# DB4100_MCU_v0_3.net
KiCad netlist of a schematic drawn in Altium Designer
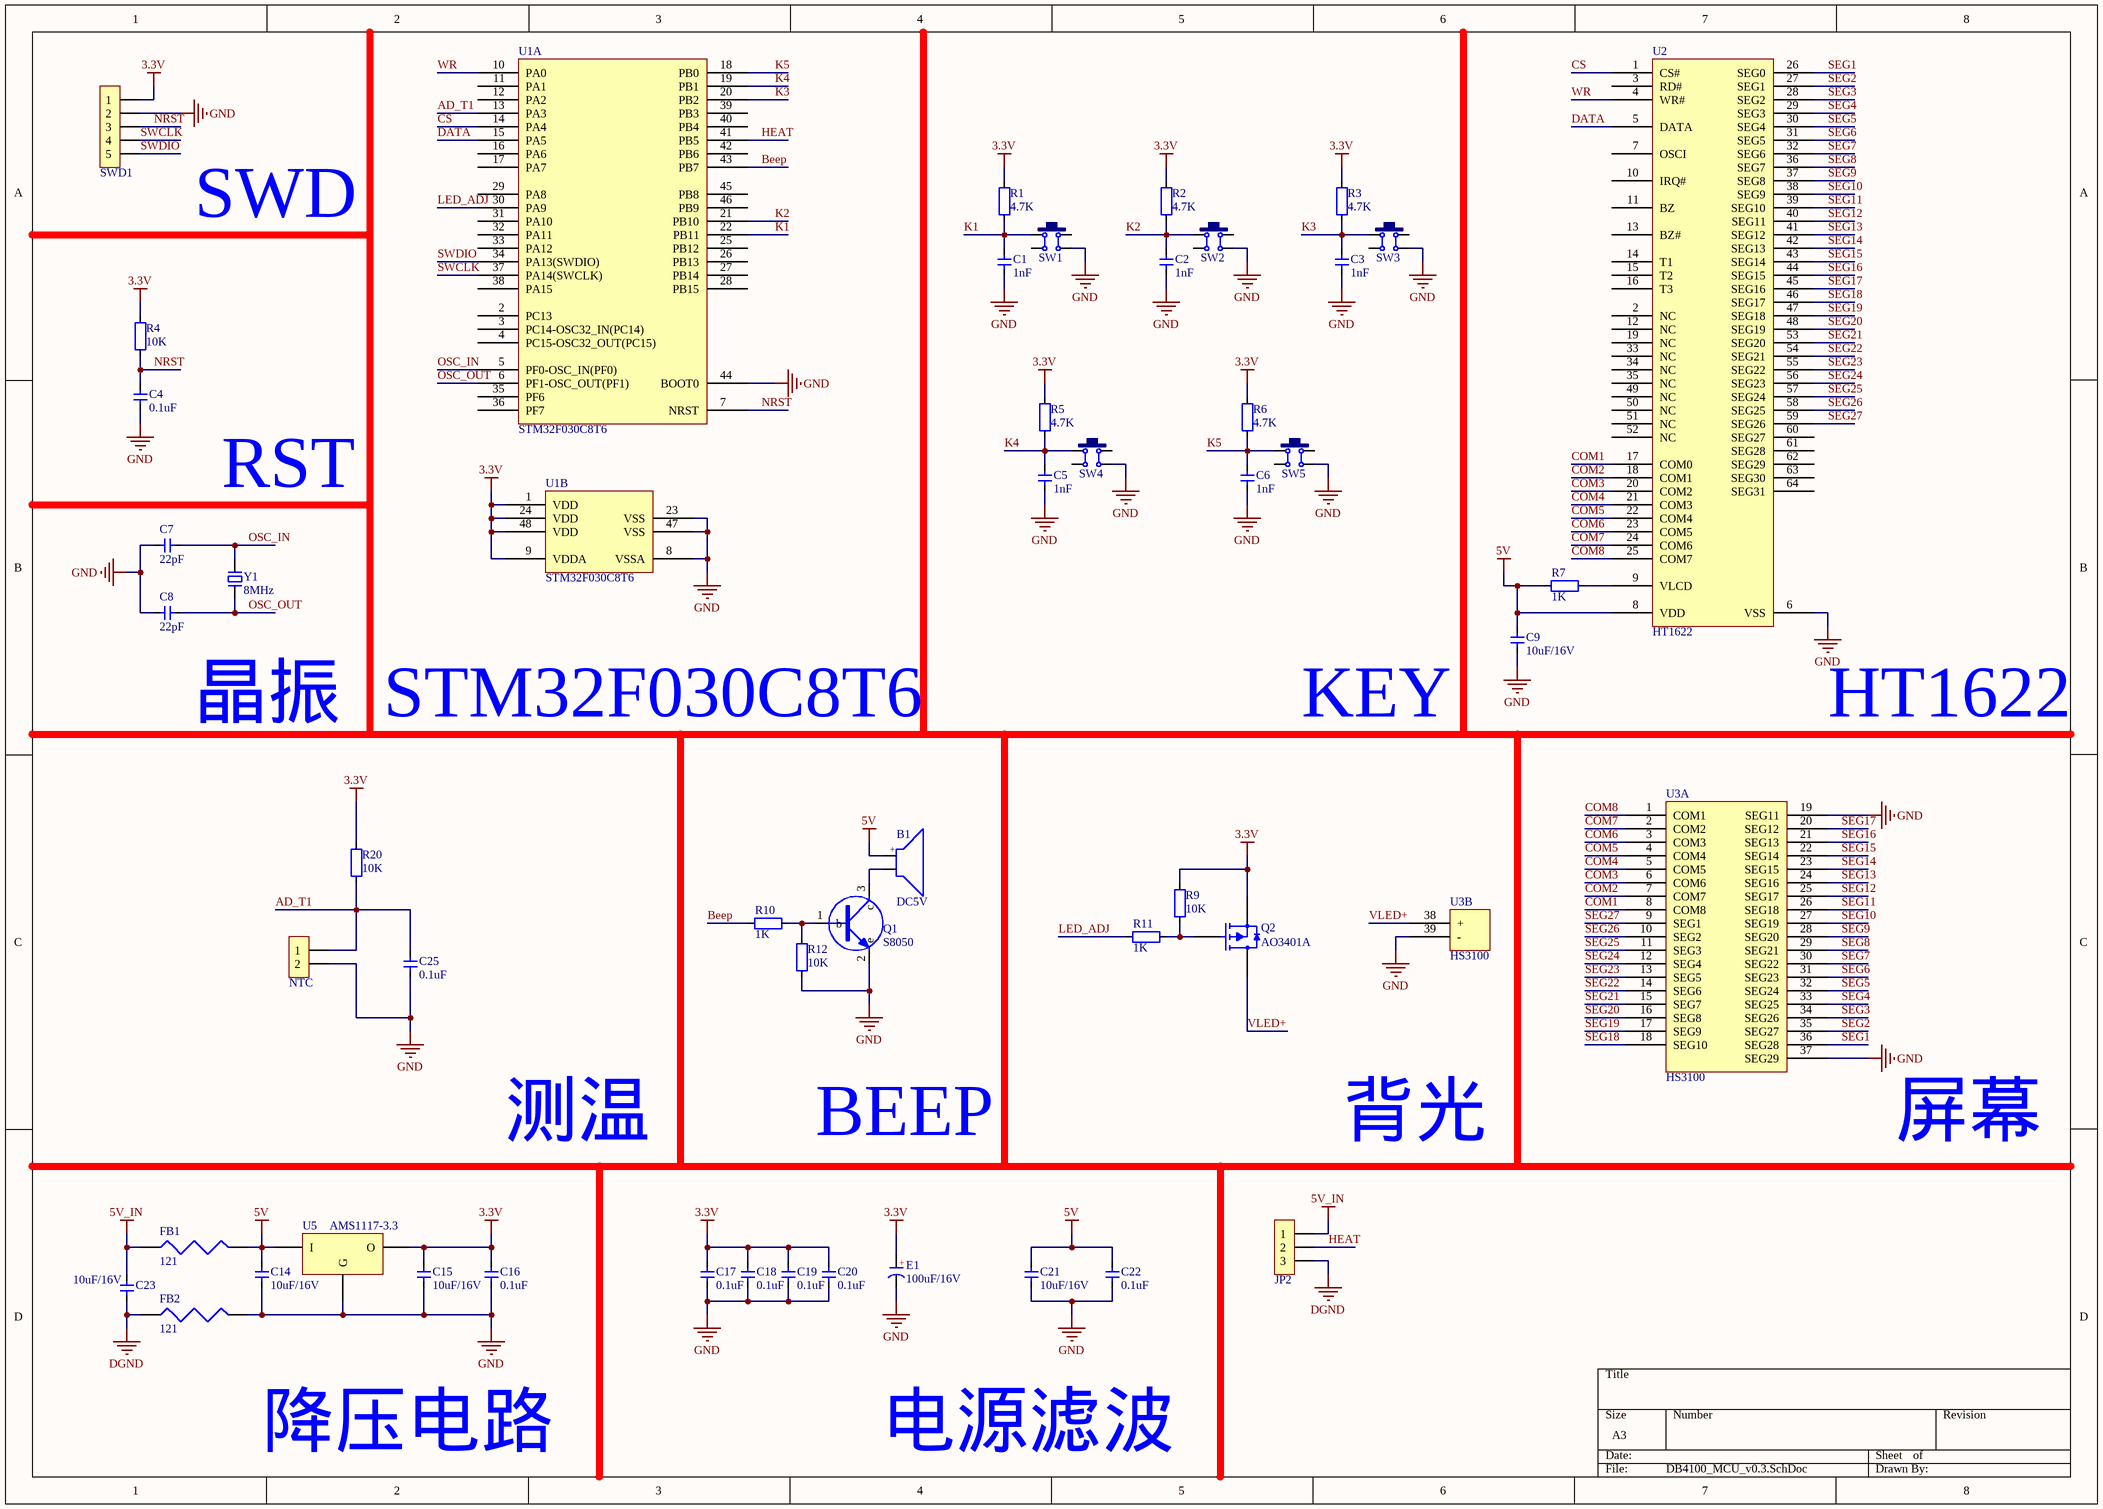
[diagram p0: DB4100_MCU_v0.3.SchDoc]

(export (version "E")
  (design (tool "Eeschema 10.0.6"))
  (components
    (comp (ref "B1")
      (value "DC5V")
      (footprint "BEEP 7.6X12X7.5")
      (description "蜂鸣器")
      (fields (field (name "版权归属") "源创客"))
      (libsource (lib "模块器件") (part "BEEP"))
    )
    (comp (ref "C1")
      (value "1nF")
      (footprint "C 0603")
      (description "无极性贴片电容")
      (fields (field (name "版权归属") "源创客"))
      (libsource (lib "电容") (part "C"))
    )
    (comp (ref "C2")
      (value "1nF")
      (footprint "C 0603")
      (description "无极性贴片电容")
      (fields (field (name "版权归属") "源创客"))
      (libsource (lib "电容") (part "C"))
    )
    (comp (ref "C3")
      (value "1nF")
      (footprint "C 0603")
      (description "无极性贴片电容")
      (fields (field (name "版权归属") "源创客"))
      (libsource (lib "电容") (part "C"))
    )
    (comp (ref "C4")
      (value "0.1uF")
      (footprint "C 0603")
      (description "无极性贴片电容")
      (fields (field (name "版权归属") "源创客"))
      (libsource (lib "电容") (part "C"))
    )
    (comp (ref "C5")
      (value "1nF")
      (footprint "C 0603")
      (description "无极性贴片电容")
      (fields (field (name "版权归属") "源创客"))
      (libsource (lib "电容") (part "C"))
    )
    (comp (ref "C6")
      (value "1nF")
      (footprint "C 0603")
      (description "无极性贴片电容")
      (fields (field (name "版权归属") "源创客"))
      (libsource (lib "电容") (part "C"))
    )
    (comp (ref "C7")
      (value "22pF")
      (footprint "C 0603")
      (description "无极性贴片电容")
      (fields (field (name "版权归属") "源创客"))
      (libsource (lib "电容") (part "C"))
    )
    (comp (ref "C8")
      (value "22pF")
      (footprint "C 0603")
      (description "无极性贴片电容")
      (fields (field (name "版权归属") "源创客"))
      (libsource (lib "电容") (part "C"))
    )
    (comp (ref "C9")
      (value "10uF/16V")
      (footprint "C 0805")
      (description "无极性贴片电容")
      (fields (field (name "版权归属") "源创客"))
      (libsource (lib "电容") (part "C"))
    )
    (comp (ref "C14")
      (value "10uF/16V")
      (footprint "C 0805")
      (description "无极性贴片电容")
      (fields (field (name "版权归属") "源创客"))
      (libsource (lib "电容") (part "C"))
    )
    (comp (ref "C15")
      (value "10uF/16V")
      (footprint "C 0805")
      (description "无极性贴片电容")
      (fields (field (name "版权归属") "源创客"))
      (libsource (lib "电容") (part "C"))
    )
    (comp (ref "C16")
      (value "0.1uF")
      (footprint "C 0603")
      (description "无极性贴片电容")
      (fields (field (name "版权归属") "源创客"))
      (libsource (lib "电容") (part "C"))
    )
    (comp (ref "C17")
      (value "0.1uF")
      (footprint "C 0603")
      (description "无极性贴片电容")
      (fields (field (name "版权归属") "源创客"))
      (libsource (lib "电容") (part "C"))
    )
    (comp (ref "C18")
      (value "0.1uF")
      (footprint "C 0603")
      (description "无极性贴片电容")
      (fields (field (name "版权归属") "源创客"))
      (libsource (lib "电容") (part "C"))
    )
    (comp (ref "C19")
      (value "0.1uF")
      (footprint "C 0603")
      (description "无极性贴片电容")
      (fields (field (name "版权归属") "源创客"))
      (libsource (lib "电容") (part "C"))
    )
    (comp (ref "C20")
      (value "0.1uF")
      (footprint "C 0603")
      (description "无极性贴片电容")
      (fields (field (name "版权归属") "源创客"))
      (libsource (lib "电容") (part "C"))
    )
    (comp (ref "C21")
      (value "10uF/16V")
      (footprint "C 0805")
      (description "无极性贴片电容")
      (fields (field (name "版权归属") "源创客"))
      (libsource (lib "电容") (part "C"))
    )
    (comp (ref "C22")
      (value "0.1uF")
      (footprint "C 0603")
      (description "无极性贴片电容")
      (fields (field (name "版权归属") "源创客"))
      (libsource (lib "电容") (part "C"))
    )
    (comp (ref "C23")
      (value "10uF/16V")
      (footprint "C 0805")
      (description "无极性贴片电容")
      (fields (field (name "版权归属") "源创客"))
      (libsource (lib "电容") (part "C"))
    )
    (comp (ref "C25")
      (value "0.1uF")
      (footprint "C 0603")
      (description "无极性贴片电容")
      (fields (field (name "版权归属") "源创客"))
      (libsource (lib "电容") (part "C"))
    )
    (comp (ref "E1")
      (value "100uF/16V")
      (footprint "CAP 2.0*5*11 - BK")
      (description "直插电解电容")
      (fields (field (name "版权归属") "源创客"))
      (libsource (lib "电容") (part "C-CAP"))
    )
    (comp (ref "FB1")
      (value "121")
      (footprint "L 0805")
      (description "磁珠")
      (libsource (lib "电感") (part "FB"))
    )
    (comp (ref "FB2")
      (value "121")
      (footprint "L 0805")
      (description "磁珠")
      (libsource (lib "电感") (part "FB"))
    )
    (comp (ref "JP2")
      (value "HDR-1X3")
      (footprint "XH2.54-3P")
      (description "3P接插件")
      (fields (field (name "版权归属") "源创客"))
      (libsource (lib "排针-排母") (part "Header 3"))
    )
    (comp (ref "NTC")
      (value "HDR-1X2")
      (footprint "XH2.54-2P")
      (description "2P接插件")
      (fields (field (name "版权归属") "源创客"))
      (libsource (lib "排针-排母") (part "Header 2"))
    )
    (comp (ref "Q1") (value "S8050") (footprint "SOT23-3L") (libsource (lib "三极管") (part "NPN")))
    (comp (ref "Q2")
      (value "AO3401A")
      (footprint "SOT23-3")
      (description "P-MOS")
      (libsource (lib "三极管") (part "AO3401A"))
    )
    (comp (ref "R1")
      (value "4.7K")
      (footprint "R 0603")
      (description "贴片电阻")
      (fields (field (name "版权归属") "源创客"))
      (libsource (lib "电阻") (part "R"))
    )
    (comp (ref "R2")
      (value "4.7K")
      (footprint "R 0603")
      (description "贴片电阻")
      (fields (field (name "版权归属") "源创客"))
      (libsource (lib "电阻") (part "R"))
    )
    (comp (ref "R3")
      (value "4.7K")
      (footprint "R 0603")
      (description "贴片电阻")
      (fields (field (name "版权归属") "源创客"))
      (libsource (lib "电阻") (part "R"))
    )
    (comp (ref "R4")
      (value "10K")
      (footprint "R 0603")
      (description "贴片电阻")
      (fields (field (name "版权归属") "源创客"))
      (libsource (lib "电阻") (part "R"))
    )
    (comp (ref "R5")
      (value "4.7K")
      (footprint "R 0603")
      (description "贴片电阻")
      (fields (field (name "版权归属") "源创客"))
      (libsource (lib "电阻") (part "R"))
    )
    (comp (ref "R6")
      (value "4.7K")
      (footprint "R 0603")
      (description "贴片电阻")
      (fields (field (name "版权归属") "源创客"))
      (libsource (lib "电阻") (part "R"))
    )
    (comp (ref "R7")
      (value "1K")
      (footprint "R 0603")
      (description "贴片电阻")
      (fields (field (name "版权归属") "源创客"))
      (libsource (lib "") (part "R_1"))
    )
    (comp (ref "R9")
      (value "10K")
      (footprint "R 0603")
      (description "贴片电阻")
      (fields (field (name "版权归属") "源创客"))
      (libsource (lib "电阻") (part "R"))
    )
    (comp (ref "R10")
      (value "1K")
      (footprint "R 0603")
      (description "贴片电阻")
      (fields (field (name "版权归属") "源创客"))
      (libsource (lib "") (part "R_1"))
    )
    (comp (ref "R11")
      (value "1K")
      (footprint "R 0603")
      (description "贴片电阻")
      (fields (field (name "版权归属") "源创客"))
      (libsource (lib "") (part "R_1"))
    )
    (comp (ref "R12")
      (value "10K")
      (footprint "R 0603")
      (description "贴片电阻")
      (fields (field (name "版权归属") "源创客"))
      (libsource (lib "电阻") (part "R"))
    )
    (comp (ref "R20")
      (value "10K")
      (footprint "R 0603")
      (description "贴片电阻")
      (fields (field (name "版权归属") "源创客"))
      (libsource (lib "电阻") (part "R"))
    )
    (comp (ref "SW1")
      (value "6x6x5")
      (footprint "TSW SMD-6*6*7")
      (description "贴片6x6轻触开关")
      (fields (field (name "版权归属") "源创客"))
      (libsource (lib "按键") (part "TSW SMD-6x6"))
    )
    (comp (ref "SW2")
      (value "6x6x5")
      (footprint "TSW SMD-6*6*7")
      (description "贴片6x6轻触开关")
      (fields (field (name "版权归属") "源创客"))
      (libsource (lib "按键") (part "TSW SMD-6x6"))
    )
    (comp (ref "SW3")
      (value "6x6x5")
      (footprint "TSW SMD-6*6*7")
      (description "贴片6x6轻触开关")
      (fields (field (name "版权归属") "源创客"))
      (libsource (lib "按键") (part "TSW SMD-6x6"))
    )
    (comp (ref "SW4")
      (value "6x6x5")
      (footprint "TSW SMD-6*6*7")
      (description "贴片6x6轻触开关")
      (fields (field (name "版权归属") "源创客"))
      (libsource (lib "按键") (part "TSW SMD-6x6"))
    )
    (comp (ref "SW5")
      (value "6x6x5")
      (footprint "TSW SMD-6*6*7")
      (description "贴片6x6轻触开关")
      (fields (field (name "版权归属") "源创客"))
      (libsource (lib "按键") (part "TSW SMD-6x6"))
    )
    (comp (ref "SWD1")
      (value "HDR-1X5")
      (footprint "XH2.54-5P")
      (description "5P接插件")
      (fields (field (name "版权归属") "源创客"))
      (libsource (lib "排针-排母") (part "Header 5"))
    )
    (comp (ref "U1")
      (value "STM32F030C8T6")
      (footprint "STM32F030C8T6")
      (libsource (lib "STM32系列单片机") (part "STM32F030C8T6"))
    )
    (comp (ref "U2")
      (value "HT1622")
      (footprint "HT1622")
      (description "LCD驱动，64引脚")
      (libsource (lib "显示芯片") (part "HT1622"))
    )
    (comp (ref "U3")
      (value "HS3100")
      (footprint "HS3100")
      (description "HS3100的屏幕")
      (libsource (lib "显示屏幕") (part "HS3100"))
    )
    (comp (ref "U5")
      (value "AMS1117-3.3")
      (footprint "AMS1117-3.3")
      (description "转3.3V电压")
      (libsource (lib "变压器") (part "AMS1117-3.3"))
    )
    (comp (ref "Y1")
      (value "8MHz")
      (footprint "XTAL-49S SMD")
      (description "2脚晶振")
      (fields (field (name "版权归属") "源创客"))
      (libsource (lib "晶振") (part "XTAL-2"))
    )
  )
  (nets
    (net (code "1") (name "/AD_T1") (class "Default")
      (node (ref "C25") (pin "1") (pinfunction "1_1") (pintype "passive"))
      (node (ref "NTC") (pin "1") (pinfunction "1_1") (pintype "passive"))
      (node (ref "R20") (pin "1") (pinfunction "1_1") (pintype "passive"))
      (node (ref "U1") (pin "13") (pinfunction "PA3_13") (pintype "passive"))
    )
    (net (code "2") (name "/Beep") (class "Default")
      (node (ref "R10") (pin "1") (pinfunction "1_1") (pintype "passive"))
      (node (ref "U1") (pin "43") (pinfunction "PB7_43") (pintype "passive"))
    )
    (net (code "3") (name "/COM1") (class "Default")
      (node (ref "U2") (pin "17") (pinfunction "COM0_17") (pintype "passive"))
      (node (ref "U3") (pin "8") (pinfunction "COM8_8") (pintype "passive"))
    )
    (net (code "4") (name "/COM2") (class "Default")
      (node (ref "U2") (pin "18") (pinfunction "COM1_18") (pintype "passive"))
      (node (ref "U3") (pin "7") (pinfunction "COM7_7") (pintype "passive"))
    )
    (net (code "5") (name "/COM3") (class "Default")
      (node (ref "U2") (pin "20") (pinfunction "COM2_20") (pintype "passive"))
      (node (ref "U3") (pin "6") (pinfunction "COM6_6") (pintype "passive"))
    )
    (net (code "6") (name "/COM4") (class "Default")
      (node (ref "U2") (pin "21") (pinfunction "COM3_21") (pintype "passive"))
      (node (ref "U3") (pin "5") (pinfunction "COM5_5") (pintype "passive"))
    )
    (net (code "7") (name "/COM5") (class "Default")
      (node (ref "U2") (pin "22") (pinfunction "COM4_22") (pintype "passive"))
      (node (ref "U3") (pin "4") (pinfunction "COM4_4") (pintype "passive"))
    )
    (net (code "8") (name "/COM6") (class "Default")
      (node (ref "U2") (pin "23") (pinfunction "COM5_23") (pintype "passive"))
      (node (ref "U3") (pin "3") (pinfunction "COM3_3") (pintype "passive"))
    )
    (net (code "9") (name "/COM7") (class "Default")
      (node (ref "U2") (pin "24") (pinfunction "COM6_24") (pintype "passive"))
      (node (ref "U3") (pin "2") (pinfunction "COM2_2") (pintype "passive"))
    )
    (net (code "10") (name "/COM8") (class "Default")
      (node (ref "U2") (pin "25") (pinfunction "COM7_25") (pintype "passive"))
      (node (ref "U3") (pin "1") (pinfunction "COM1_1") (pintype "passive"))
    )
    (net (code "11") (name "/CS") (class "Default")
      (node (ref "U1") (pin "14") (pinfunction "PA4_14") (pintype "passive"))
      (node (ref "U2") (pin "1") (pinfunction "CS#_1") (pintype "passive"))
    )
    (net (code "12") (name "/DATA") (class "Default")
      (node (ref "U1") (pin "15") (pinfunction "PA5_15") (pintype "passive"))
      (node (ref "U2") (pin "5") (pinfunction "DATA_5") (pintype "passive"))
    )
    (net (code "13") (name "/HEAT") (class "Default")
      (node (ref "JP2") (pin "2") (pinfunction "2_2") (pintype "passive"))
      (node (ref "U1") (pin "41") (pinfunction "PB5_41") (pintype "passive"))
    )
    (net (code "14") (name "/K1") (class "Default")
      (node (ref "C1") (pin "2") (pinfunction "2_2") (pintype "passive"))
      (node (ref "R1") (pin "1") (pinfunction "1_1") (pintype "passive"))
      (node (ref "SW1") (pin "1") (pinfunction "1_1") (pintype "passive"))
      (node (ref "U1") (pin "22") (pinfunction "PB11_22") (pintype "passive"))
    )
    (net (code "15") (name "/K2") (class "Default")
      (node (ref "C2") (pin "2") (pinfunction "2_2") (pintype "passive"))
      (node (ref "R2") (pin "1") (pinfunction "1_1") (pintype "passive"))
      (node (ref "SW2") (pin "1") (pinfunction "1_1") (pintype "passive"))
      (node (ref "U1") (pin "21") (pinfunction "PB10_21") (pintype "passive"))
    )
    (net (code "16") (name "/K3") (class "Default")
      (node (ref "C3") (pin "2") (pinfunction "2_2") (pintype "passive"))
      (node (ref "R3") (pin "1") (pinfunction "1_1") (pintype "passive"))
      (node (ref "SW3") (pin "1") (pinfunction "1_1") (pintype "passive"))
      (node (ref "U1") (pin "20") (pinfunction "PB2_20") (pintype "passive"))
    )
    (net (code "17") (name "/K4") (class "Default")
      (node (ref "C5") (pin "2") (pinfunction "2_2") (pintype "passive"))
      (node (ref "R5") (pin "1") (pinfunction "1_1") (pintype "passive"))
      (node (ref "SW4") (pin "1") (pinfunction "1_1") (pintype "passive"))
      (node (ref "U1") (pin "19") (pinfunction "PB1_19") (pintype "passive"))
    )
    (net (code "18") (name "/K5") (class "Default")
      (node (ref "C6") (pin "2") (pinfunction "2_2") (pintype "passive"))
      (node (ref "R6") (pin "1") (pinfunction "1_1") (pintype "passive"))
      (node (ref "SW5") (pin "1") (pinfunction "1_1") (pintype "passive"))
      (node (ref "U1") (pin "18") (pinfunction "PB0_18") (pintype "passive"))
    )
    (net (code "19") (name "/LED_ADJ") (class "Default")
      (node (ref "R11") (pin "1") (pinfunction "1_1") (pintype "passive"))
      (node (ref "U1") (pin "30") (pinfunction "PA9_30") (pintype "passive"))
    )
    (net (code "20") (name "/NRST") (class "Default")
      (node (ref "C4") (pin "2") (pinfunction "2_2") (pintype "passive"))
      (node (ref "R4") (pin "1") (pinfunction "1_1") (pintype "passive"))
      (node (ref "SWD1") (pin "3") (pinfunction "3_3") (pintype "passive"))
      (node (ref "U1") (pin "7") (pinfunction "NRST_7") (pintype "passive"))
    )
    (net (code "21") (name "/OSC_IN") (class "Default")
      (node (ref "C7") (pin "2") (pinfunction "2_2") (pintype "passive"))
      (node (ref "U1") (pin "5") (pinfunction "PF0-OSC_IN(PF0)_5") (pintype "passive"))
      (node (ref "Y1") (pin "2") (pinfunction "2_2") (pintype "passive"))
    )
    (net (code "22") (name "/OSC_OUT") (class "Default")
      (node (ref "C8") (pin "2") (pinfunction "2_2") (pintype "passive"))
      (node (ref "U1") (pin "6") (pinfunction "PF1-OSC_OUT(PF1)_6") (pintype "passive"))
      (node (ref "Y1") (pin "1") (pinfunction "1_1") (pintype "passive"))
    )
    (net (code "23") (name "/SEG1") (class "Default")
      (node (ref "U2") (pin "26") (pinfunction "SEG0_26") (pintype "passive"))
      (node (ref "U3") (pin "36") (pinfunction "SEG28_36") (pintype "passive"))
    )
    (net (code "24") (name "/SEG2") (class "Default")
      (node (ref "U2") (pin "27") (pinfunction "SEG1_27") (pintype "passive"))
      (node (ref "U3") (pin "35") (pinfunction "SEG27_35") (pintype "passive"))
    )
    (net (code "25") (name "/SEG3") (class "Default")
      (node (ref "U2") (pin "28") (pinfunction "SEG2_28") (pintype "passive"))
      (node (ref "U3") (pin "34") (pinfunction "SEG26_34") (pintype "passive"))
    )
    (net (code "26") (name "/SEG4") (class "Default")
      (node (ref "U2") (pin "29") (pinfunction "SEG3_29") (pintype "passive"))
      (node (ref "U3") (pin "33") (pinfunction "SEG25_33") (pintype "passive"))
    )
    (net (code "27") (name "/SEG5") (class "Default")
      (node (ref "U2") (pin "30") (pinfunction "SEG4_30") (pintype "passive"))
      (node (ref "U3") (pin "32") (pinfunction "SEG24_32") (pintype "passive"))
    )
    (net (code "28") (name "/SEG6") (class "Default")
      (node (ref "U2") (pin "31") (pinfunction "SEG5_31") (pintype "passive"))
      (node (ref "U3") (pin "31") (pinfunction "SEG23_31") (pintype "passive"))
    )
    (net (code "29") (name "/SEG7") (class "Default")
      (node (ref "U2") (pin "32") (pinfunction "SEG6_32") (pintype "passive"))
      (node (ref "U3") (pin "30") (pinfunction "SEG22_30") (pintype "passive"))
    )
    (net (code "30") (name "/SEG8") (class "Default")
      (node (ref "U2") (pin "36") (pinfunction "SEG7_36") (pintype "passive"))
      (node (ref "U3") (pin "29") (pinfunction "SEG21_29") (pintype "passive"))
    )
    (net (code "31") (name "/SEG9") (class "Default")
      (node (ref "U2") (pin "37") (pinfunction "SEG8_37") (pintype "passive"))
      (node (ref "U3") (pin "28") (pinfunction "SEG20_28") (pintype "passive"))
    )
    (net (code "32") (name "/SEG10") (class "Default")
      (node (ref "U2") (pin "38") (pinfunction "SEG9_38") (pintype "passive"))
      (node (ref "U3") (pin "27") (pinfunction "SEG19_27") (pintype "passive"))
    )
    (net (code "33") (name "/SEG11") (class "Default")
      (node (ref "U2") (pin "39") (pinfunction "SEG10_39") (pintype "passive"))
      (node (ref "U3") (pin "26") (pinfunction "SEG18_26") (pintype "passive"))
    )
    (net (code "34") (name "/SEG12") (class "Default")
      (node (ref "U2") (pin "40") (pinfunction "SEG11_40") (pintype "passive"))
      (node (ref "U3") (pin "25") (pinfunction "SEG17_25") (pintype "passive"))
    )
    (net (code "35") (name "/SEG13") (class "Default")
      (node (ref "U2") (pin "41") (pinfunction "SEG12_41") (pintype "passive"))
      (node (ref "U3") (pin "24") (pinfunction "SEG16_24") (pintype "passive"))
    )
    (net (code "36") (name "/SEG14") (class "Default")
      (node (ref "U2") (pin "42") (pinfunction "SEG13_42") (pintype "passive"))
      (node (ref "U3") (pin "23") (pinfunction "SEG15_23") (pintype "passive"))
    )
    (net (code "37") (name "/SEG15") (class "Default")
      (node (ref "U2") (pin "43") (pinfunction "SEG14_43") (pintype "passive"))
      (node (ref "U3") (pin "22") (pinfunction "SEG14_22") (pintype "passive"))
    )
    (net (code "38") (name "/SEG16") (class "Default")
      (node (ref "U2") (pin "44") (pinfunction "SEG15_44") (pintype "passive"))
      (node (ref "U3") (pin "21") (pinfunction "SEG13_21") (pintype "passive"))
    )
    (net (code "39") (name "/SEG17") (class "Default")
      (node (ref "U2") (pin "45") (pinfunction "SEG16_45") (pintype "passive"))
      (node (ref "U3") (pin "20") (pinfunction "SEG12_20") (pintype "passive"))
    )
    (net (code "40") (name "/SEG18") (class "Default")
      (node (ref "U2") (pin "46") (pinfunction "SEG17_46") (pintype "passive"))
      (node (ref "U3") (pin "18") (pinfunction "SEG10_18") (pintype "passive"))
    )
    (net (code "41") (name "/SEG19") (class "Default")
      (node (ref "U2") (pin "47") (pinfunction "SEG18_47") (pintype "passive"))
      (node (ref "U3") (pin "17") (pinfunction "SEG9_17") (pintype "passive"))
    )
    (net (code "42") (name "/SEG20") (class "Default")
      (node (ref "U2") (pin "48") (pinfunction "SEG19_48") (pintype "passive"))
      (node (ref "U3") (pin "16") (pinfunction "SEG8_16") (pintype "passive"))
    )
    (net (code "43") (name "/SEG21") (class "Default")
      (node (ref "U2") (pin "53") (pinfunction "SEG20_53") (pintype "passive"))
      (node (ref "U3") (pin "15") (pinfunction "SEG7_15") (pintype "passive"))
    )
    (net (code "44") (name "/SEG22") (class "Default")
      (node (ref "U2") (pin "54") (pinfunction "SEG21_54") (pintype "passive"))
      (node (ref "U3") (pin "14") (pinfunction "SEG6_14") (pintype "passive"))
    )
    (net (code "45") (name "/SEG23") (class "Default")
      (node (ref "U2") (pin "55") (pinfunction "SEG22_55") (pintype "passive"))
      (node (ref "U3") (pin "13") (pinfunction "SEG5_13") (pintype "passive"))
    )
    (net (code "46") (name "/SEG24") (class "Default")
      (node (ref "U2") (pin "56") (pinfunction "SEG23_56") (pintype "passive"))
      (node (ref "U3") (pin "12") (pinfunction "SEG4_12") (pintype "passive"))
    )
    (net (code "47") (name "/SEG25") (class "Default")
      (node (ref "U2") (pin "57") (pinfunction "SEG24_57") (pintype "passive"))
      (node (ref "U3") (pin "11") (pinfunction "SEG3_11") (pintype "passive"))
    )
    (net (code "48") (name "/SEG26") (class "Default")
      (node (ref "U2") (pin "58") (pinfunction "SEG25_58") (pintype "passive"))
      (node (ref "U3") (pin "10") (pinfunction "SEG2_10") (pintype "passive"))
    )
    (net (code "49") (name "/SEG27") (class "Default")
      (node (ref "U2") (pin "59") (pinfunction "SEG26_59") (pintype "passive"))
      (node (ref "U3") (pin "9") (pinfunction "SEG1_9") (pintype "passive"))
    )
    (net (code "50") (name "/SWCLK") (class "Default")
      (node (ref "SWD1") (pin "4") (pinfunction "4_4") (pintype "passive"))
      (node (ref "U1") (pin "37") (pinfunction "PA14(SWCLK)_37") (pintype "passive"))
    )
    (net (code "51") (name "/SWDIO") (class "Default")
      (node (ref "SWD1") (pin "5") (pinfunction "5_5") (pintype "passive"))
      (node (ref "U1") (pin "34") (pinfunction "PA13(SWDIO)_34") (pintype "passive"))
    )
    (net (code "52") (name "/VLED+") (class "Default")
      (node (ref "Q2") (pin "3") (pinfunction "D_3") (pintype "passive"))
      (node (ref "U3") (pin "38") (pinfunction "+_38") (pintype "passive"))
    )
    (net (code "53") (name "/WR") (class "Default")
      (node (ref "U1") (pin "10") (pinfunction "PA0_10") (pintype "passive"))
      (node (ref "U2") (pin "4") (pinfunction "WR#_4") (pintype "passive"))
    )
    (net (code "54") (name "3.3V") (class "Default")
      (node (ref "C15") (pin "2") (pinfunction "2_2") (pintype "passive"))
      (node (ref "C16") (pin "2") (pinfunction "2_2") (pintype "passive"))
      (node (ref "C17") (pin "2") (pinfunction "2_2") (pintype "passive"))
      (node (ref "C18") (pin "2") (pinfunction "2_2") (pintype "passive"))
      (node (ref "C19") (pin "2") (pinfunction "2_2") (pintype "passive"))
      (node (ref "C20") (pin "2") (pinfunction "2_2") (pintype "passive"))
      (node (ref "E1") (pin "1") (pinfunction "A_1") (pintype "passive"))
      (node (ref "Q2") (pin "2") (pinfunction "S_2") (pintype "passive"))
      (node (ref "R1") (pin "2") (pinfunction "2_2") (pintype "passive"))
      (node (ref "R2") (pin "2") (pinfunction "2_2") (pintype "passive"))
      (node (ref "R20") (pin "2") (pinfunction "2_2") (pintype "passive"))
      (node (ref "R3") (pin "2") (pinfunction "2_2") (pintype "passive"))
      (node (ref "R4") (pin "2") (pinfunction "2_2") (pintype "passive"))
      (node (ref "R5") (pin "2") (pinfunction "2_2") (pintype "passive"))
      (node (ref "R6") (pin "2") (pinfunction "2_2") (pintype "passive"))
      (node (ref "R9") (pin "2") (pinfunction "2_2") (pintype "passive"))
      (node (ref "SWD1") (pin "1") (pinfunction "1_1") (pintype "passive"))
      (node (ref "U1") (pin "1") (pinfunction "VDD_1") (pintype "passive"))
      (node (ref "U1") (pin "24") (pinfunction "VDD_24") (pintype "passive"))
      (node (ref "U1") (pin "48") (pinfunction "VDD_48") (pintype "passive"))
      (node (ref "U1") (pin "9") (pinfunction "VDDA_9") (pintype "passive"))
      (node (ref "U5") (pin "2") (pinfunction "O_2") (pintype "passive"))
    )
    (net (code "55") (name "5V") (class "Default")
      (node (ref "B1") (pin "1") (pinfunction "1_1") (pintype "passive"))
      (node (ref "C14") (pin "2") (pinfunction "2_2") (pintype "passive"))
      (node (ref "C21") (pin "2") (pinfunction "2_2") (pintype "passive"))
      (node (ref "C22") (pin "2") (pinfunction "2_2") (pintype "passive"))
      (node (ref "C9") (pin "2") (pinfunction "2_2") (pintype "passive"))
      (node (ref "FB1") (pin "2") (pinfunction "2_2") (pintype "passive"))
      (node (ref "R7") (pin "1") (pinfunction "1_1") (pintype "passive"))
      (node (ref "U2") (pin "8") (pinfunction "VDD_8") (pintype "passive"))
      (node (ref "U5") (pin "3") (pinfunction "I_3") (pintype "passive"))
    )
    (net (code "56") (name "5V_IN") (class "Default")
      (node (ref "C23") (pin "2") (pinfunction "2_2") (pintype "passive"))
      (node (ref "FB1") (pin "1") (pinfunction "1_1") (pintype "passive"))
      (node (ref "JP2") (pin "1") (pinfunction "1_1") (pintype "passive"))
    )
    (net (code "57") (name "DGND") (class "Default")
      (node (ref "C23") (pin "1") (pinfunction "1_1") (pintype "passive"))
      (node (ref "FB2") (pin "1") (pinfunction "1_1") (pintype "passive"))
      (node (ref "JP2") (pin "3") (pinfunction "3_3") (pintype "passive"))
    )
    (net (code "58") (name "GND") (class "Default")
      (node (ref "C1") (pin "1") (pinfunction "1_1") (pintype "passive"))
      (node (ref "C14") (pin "1") (pinfunction "1_1") (pintype "passive"))
      (node (ref "C15") (pin "1") (pinfunction "1_1") (pintype "passive"))
      (node (ref "C16") (pin "1") (pinfunction "1_1") (pintype "passive"))
      (node (ref "C17") (pin "1") (pinfunction "1_1") (pintype "passive"))
      (node (ref "C18") (pin "1") (pinfunction "1_1") (pintype "passive"))
      (node (ref "C19") (pin "1") (pinfunction "1_1") (pintype "passive"))
      (node (ref "C2") (pin "1") (pinfunction "1_1") (pintype "passive"))
      (node (ref "C20") (pin "1") (pinfunction "1_1") (pintype "passive"))
      (node (ref "C21") (pin "1") (pinfunction "1_1") (pintype "passive"))
      (node (ref "C22") (pin "1") (pinfunction "1_1") (pintype "passive"))
      (node (ref "C25") (pin "2") (pinfunction "2_2") (pintype "passive"))
      (node (ref "C3") (pin "1") (pinfunction "1_1") (pintype "passive"))
      (node (ref "C4") (pin "1") (pinfunction "1_1") (pintype "passive"))
      (node (ref "C5") (pin "1") (pinfunction "1_1") (pintype "passive"))
      (node (ref "C6") (pin "1") (pinfunction "1_1") (pintype "passive"))
      (node (ref "C7") (pin "1") (pinfunction "1_1") (pintype "passive"))
      (node (ref "C8") (pin "1") (pinfunction "1_1") (pintype "passive"))
      (node (ref "C9") (pin "1") (pinfunction "1_1") (pintype "passive"))
      (node (ref "E1") (pin "2") (pinfunction "K_2") (pintype "passive"))
      (node (ref "FB2") (pin "2") (pinfunction "2_2") (pintype "passive"))
      (node (ref "NTC") (pin "2") (pinfunction "2_2") (pintype "passive"))
      (node (ref "Q1") (pin "2") (pinfunction "e_2") (pintype "passive"))
      (node (ref "R12") (pin "1") (pinfunction "1_1") (pintype "passive"))
      (node (ref "SW1") (pin "3") (pinfunction "3_3") (pintype "passive"))
      (node (ref "SW2") (pin "3") (pinfunction "3_3") (pintype "passive"))
      (node (ref "SW3") (pin "3") (pinfunction "3_3") (pintype "passive"))
      (node (ref "SW4") (pin "3") (pinfunction "3_3") (pintype "passive"))
      (node (ref "SW5") (pin "3") (pinfunction "3_3") (pintype "passive"))
      (node (ref "SWD1") (pin "2") (pinfunction "2_2") (pintype "passive"))
      (node (ref "U1") (pin "23") (pinfunction "VSS_23") (pintype "passive"))
      (node (ref "U1") (pin "44") (pinfunction "BOOT0_44") (pintype "passive"))
      (node (ref "U1") (pin "47") (pinfunction "VSS_47") (pintype "passive"))
      (node (ref "U1") (pin "8") (pinfunction "VSSA_8") (pintype "passive"))
      (node (ref "U2") (pin "6") (pinfunction "VSS_6") (pintype "passive"))
      (node (ref "U3") (pin "19") (pinfunction "SEG11_19") (pintype "passive"))
      (node (ref "U3") (pin "37") (pinfunction "SEG29_37") (pintype "passive"))
      (node (ref "U3") (pin "39") (pinfunction "-_39") (pintype "passive"))
      (node (ref "U5") (pin "1") (pinfunction "G_1") (pintype "passive"))
    )
    (net (code "59") (name "Net-(Q1-b)") (class "Default")
      (node (ref "Q1") (pin "1") (pinfunction "b_1") (pintype "passive"))
      (node (ref "R10") (pin "2") (pinfunction "2_2") (pintype "passive"))
      (node (ref "R12") (pin "2") (pinfunction "2_2") (pintype "passive"))
    )
    (net (code "60") (name "Net-(Q1-c)") (class "Default")
      (node (ref "B1") (pin "2") (pinfunction "2_2") (pintype "passive"))
      (node (ref "Q1") (pin "3") (pinfunction "c_3") (pintype "passive"))
    )
    (net (code "61") (name "Net-(Q2-G)") (class "Default")
      (node (ref "Q2") (pin "1") (pinfunction "G_1") (pintype "passive"))
      (node (ref "R11") (pin "2") (pinfunction "2_2") (pintype "passive"))
      (node (ref "R9") (pin "1") (pinfunction "1_1") (pintype "passive"))
    )
    (net (code "62") (name "Net-(U2-VLCD)") (class "Default")
      (node (ref "R7") (pin "2") (pinfunction "2_2") (pintype "passive"))
      (node (ref "U2") (pin "9") (pinfunction "VLCD_9") (pintype "passive"))
    )
    (net (code "63") (name "unconnected-(SW1-Pad2)") (class "Default")
      (node (ref "SW1") (pin "2") (pinfunction "2_2") (pintype "passive"))
    )
    (net (code "64") (name "unconnected-(SW1-Pad4)") (class "Default")
      (node (ref "SW1") (pin "4") (pinfunction "4_4") (pintype "passive"))
    )
    (net (code "65") (name "unconnected-(SW2-Pad2)") (class "Default")
      (node (ref "SW2") (pin "2") (pinfunction "2_2") (pintype "passive"))
    )
    (net (code "66") (name "unconnected-(SW2-Pad4)") (class "Default")
      (node (ref "SW2") (pin "4") (pinfunction "4_4") (pintype "passive"))
    )
    (net (code "67") (name "unconnected-(SW3-Pad2)") (class "Default")
      (node (ref "SW3") (pin "2") (pinfunction "2_2") (pintype "passive"))
    )
    (net (code "68") (name "unconnected-(SW3-Pad4)") (class "Default")
      (node (ref "SW3") (pin "4") (pinfunction "4_4") (pintype "passive"))
    )
    (net (code "69") (name "unconnected-(SW4-Pad2)") (class "Default")
      (node (ref "SW4") (pin "2") (pinfunction "2_2") (pintype "passive"))
    )
    (net (code "70") (name "unconnected-(SW4-Pad4)") (class "Default")
      (node (ref "SW4") (pin "4") (pinfunction "4_4") (pintype "passive"))
    )
    (net (code "71") (name "unconnected-(SW5-Pad2)") (class "Default")
      (node (ref "SW5") (pin "2") (pinfunction "2_2") (pintype "passive"))
    )
    (net (code "72") (name "unconnected-(SW5-Pad4)") (class "Default")
      (node (ref "SW5") (pin "4") (pinfunction "4_4") (pintype "passive"))
    )
    (net (code "73") (name "unconnected-(U1A-PA1-Pad11)") (class "Default")
      (node (ref "U1") (pin "11") (pinfunction "PA1_11") (pintype "passive"))
    )
    (net (code "74") (name "unconnected-(U1A-PA2-Pad12)") (class "Default")
      (node (ref "U1") (pin "12") (pinfunction "PA2_12") (pintype "passive"))
    )
    (net (code "75") (name "unconnected-(U1A-PA6-Pad16)") (class "Default")
      (node (ref "U1") (pin "16") (pinfunction "PA6_16") (pintype "passive"))
    )
    (net (code "76") (name "unconnected-(U1A-PA7-Pad17)") (class "Default")
      (node (ref "U1") (pin "17") (pinfunction "PA7_17") (pintype "passive"))
    )
    (net (code "77") (name "unconnected-(U1A-PA8-Pad29)") (class "Default")
      (node (ref "U1") (pin "29") (pinfunction "PA8_29") (pintype "passive"))
    )
    (net (code "78") (name "unconnected-(U1A-PA10-Pad31)") (class "Default")
      (node (ref "U1") (pin "31") (pinfunction "PA10_31") (pintype "passive"))
    )
    (net (code "79") (name "unconnected-(U1A-PA11-Pad32)") (class "Default")
      (node (ref "U1") (pin "32") (pinfunction "PA11_32") (pintype "passive"))
    )
    (net (code "80") (name "unconnected-(U1A-PA12-Pad33)") (class "Default")
      (node (ref "U1") (pin "33") (pinfunction "PA12_33") (pintype "passive"))
    )
    (net (code "81") (name "unconnected-(U1A-PA15-Pad38)") (class "Default")
      (node (ref "U1") (pin "38") (pinfunction "PA15_38") (pintype "passive"))
    )
    (net (code "82") (name "unconnected-(U1A-PB3-Pad39)") (class "Default")
      (node (ref "U1") (pin "39") (pinfunction "PB3_39") (pintype "passive"))
    )
    (net (code "83") (name "unconnected-(U1A-PB4-Pad40)") (class "Default")
      (node (ref "U1") (pin "40") (pinfunction "PB4_40") (pintype "passive"))
    )
    (net (code "84") (name "unconnected-(U1A-PB6-Pad42)") (class "Default")
      (node (ref "U1") (pin "42") (pinfunction "PB6_42") (pintype "passive"))
    )
    (net (code "85") (name "unconnected-(U1A-PB8-Pad45)") (class "Default")
      (node (ref "U1") (pin "45") (pinfunction "PB8_45") (pintype "passive"))
    )
    (net (code "86") (name "unconnected-(U1A-PB9-Pad46)") (class "Default")
      (node (ref "U1") (pin "46") (pinfunction "PB9_46") (pintype "passive"))
    )
    (net (code "87") (name "unconnected-(U1A-PB12-Pad25)") (class "Default")
      (node (ref "U1") (pin "25") (pinfunction "PB12_25") (pintype "passive"))
    )
    (net (code "88") (name "unconnected-(U1A-PB13-Pad26)") (class "Default")
      (node (ref "U1") (pin "26") (pinfunction "PB13_26") (pintype "passive"))
    )
    (net (code "89") (name "unconnected-(U1A-PB14-Pad27)") (class "Default")
      (node (ref "U1") (pin "27") (pinfunction "PB14_27") (pintype "passive"))
    )
    (net (code "90") (name "unconnected-(U1A-PB15-Pad28)") (class "Default")
      (node (ref "U1") (pin "28") (pinfunction "PB15_28") (pintype "passive"))
    )
    (net (code "91") (name "unconnected-(U1A-PC13-Pad2)") (class "Default")
      (node (ref "U1") (pin "2") (pinfunction "PC13_2") (pintype "passive"))
    )
    (net (code "92") (name "unconnected-(U1A-PC14-OSC32_IN(PC14)-Pad3)") (class "Default")
      (node (ref "U1") (pin "3") (pinfunction "PC14-OSC32_IN(PC14)_3") (pintype "passive"))
    )
    (net (code "93") (name "unconnected-(U1A-PC15-OSC32_OUT(PC15)-Pad4)") (class "Default")
      (node (ref "U1") (pin "4") (pinfunction "PC15-OSC32_OUT(PC15)_4") (pintype "passive"))
    )
    (net (code "94") (name "unconnected-(U1A-PF6-Pad35)") (class "Default")
      (node (ref "U1") (pin "35") (pinfunction "PF6_35") (pintype "passive"))
    )
    (net (code "95") (name "unconnected-(U1A-PF7-Pad36)") (class "Default")
      (node (ref "U1") (pin "36") (pinfunction "PF7_36") (pintype "passive"))
    )
    (net (code "96") (name "unconnected-(U2-BZ#-Pad13)") (class "Default")
      (node (ref "U2") (pin "13") (pinfunction "BZ#_13") (pintype "passive"))
    )
    (net (code "97") (name "unconnected-(U2-BZ-Pad11)") (class "Default")
      (node (ref "U2") (pin "11") (pinfunction "BZ_11") (pintype "passive"))
    )
    (net (code "98") (name "unconnected-(U2-IRQ#-Pad10)") (class "Default")
      (node (ref "U2") (pin "10") (pinfunction "IRQ#_10") (pintype "passive"))
    )
    (net (code "99") (name "unconnected-(U2-NC-Pad2)") (class "Default")
      (node (ref "U2") (pin "2") (pinfunction "NC_2") (pintype "passive"))
    )
    (net (code "100") (name "unconnected-(U2-NC-Pad12)") (class "Default")
      (node (ref "U2") (pin "12") (pinfunction "NC_12") (pintype "passive"))
    )
    (net (code "101") (name "unconnected-(U2-NC-Pad19)") (class "Default")
      (node (ref "U2") (pin "19") (pinfunction "NC_19") (pintype "passive"))
    )
    (net (code "102") (name "unconnected-(U2-NC-Pad33)") (class "Default")
      (node (ref "U2") (pin "33") (pinfunction "NC_33") (pintype "passive"))
    )
    (net (code "103") (name "unconnected-(U2-NC-Pad34)") (class "Default")
      (node (ref "U2") (pin "34") (pinfunction "NC_34") (pintype "passive"))
    )
    (net (code "104") (name "unconnected-(U2-NC-Pad35)") (class "Default")
      (node (ref "U2") (pin "35") (pinfunction "NC_35") (pintype "passive"))
    )
    (net (code "105") (name "unconnected-(U2-NC-Pad49)") (class "Default")
      (node (ref "U2") (pin "49") (pinfunction "NC_49") (pintype "passive"))
    )
    (net (code "106") (name "unconnected-(U2-NC-Pad50)") (class "Default")
      (node (ref "U2") (pin "50") (pinfunction "NC_50") (pintype "passive"))
    )
    (net (code "107") (name "unconnected-(U2-NC-Pad51)") (class "Default")
      (node (ref "U2") (pin "51") (pinfunction "NC_51") (pintype "passive"))
    )
    (net (code "108") (name "unconnected-(U2-NC-Pad52)") (class "Default")
      (node (ref "U2") (pin "52") (pinfunction "NC_52") (pintype "passive"))
    )
    (net (code "109") (name "unconnected-(U2-OSCI-Pad7)") (class "Default")
      (node (ref "U2") (pin "7") (pinfunction "OSCI_7") (pintype "passive"))
    )
    (net (code "110") (name "unconnected-(U2-RD#-Pad3)") (class "Default")
      (node (ref "U2") (pin "3") (pinfunction "RD#_3") (pintype "passive"))
    )
    (net (code "111") (name "unconnected-(U2-SEG27-Pad60)") (class "Default")
      (node (ref "U2") (pin "60") (pinfunction "SEG27_60") (pintype "passive"))
    )
    (net (code "112") (name "unconnected-(U2-SEG28-Pad61)") (class "Default")
      (node (ref "U2") (pin "61") (pinfunction "SEG28_61") (pintype "passive"))
    )
    (net (code "113") (name "unconnected-(U2-SEG29-Pad62)") (class "Default")
      (node (ref "U2") (pin "62") (pinfunction "SEG29_62") (pintype "passive"))
    )
    (net (code "114") (name "unconnected-(U2-SEG30-Pad63)") (class "Default")
      (node (ref "U2") (pin "63") (pinfunction "SEG30_63") (pintype "passive"))
    )
    (net (code "115") (name "unconnected-(U2-SEG31-Pad64)") (class "Default")
      (node (ref "U2") (pin "64") (pinfunction "SEG31_64") (pintype "passive"))
    )
    (net (code "116") (name "unconnected-(U2-T1-Pad14)") (class "Default")
      (node (ref "U2") (pin "14") (pinfunction "T1_14") (pintype "passive"))
    )
    (net (code "117") (name "unconnected-(U2-T2-Pad15)") (class "Default")
      (node (ref "U2") (pin "15") (pinfunction "T2_15") (pintype "passive"))
    )
    (net (code "118") (name "unconnected-(U2-T3-Pad16)") (class "Default")
      (node (ref "U2") (pin "16") (pinfunction "T3_16") (pintype "passive"))
    )
  )
)
